# TPS6273x.net
KiCad netlist of a schematic drawn in EAGLE
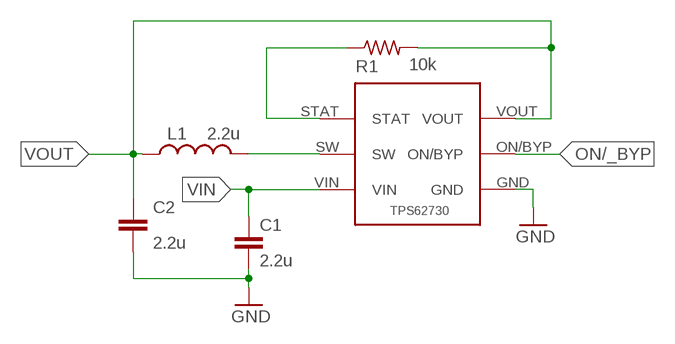
[diagram p0: schematic, sheet 1]

(export (version "E")
  (design (tool "Eeschema 10.0.6"))
  (components
    (comp (ref "C1")
      (value "2.2u")
      (footprint "eagle-import:C0603")
      (libsource (lib "eagle-import") (part "C-EUC0603"))
    )
    (comp (ref "C2")
      (value "2.2u")
      (footprint "eagle-import:C0603")
      (libsource (lib "eagle-import") (part "C-EUC0603"))
    )
    (comp (ref "L1")
      (value "2.2u")
      (footprint "eagle-import:L1210")
      (libsource (lib "eagle-import") (part "L-USL1210"))
    )
    (comp (ref "R1")
      (value "10k")
      (footprint "eagle-import:R0603")
      (libsource (lib "eagle-import") (part "R-US_R0603"))
    )
    (comp (ref "U$1")
      (value "TPS62730")
      (footprint "eagle-import:TPS62730")
      (libsource (lib "eagle-import") (part "TPS62730"))
    )
  )
  (nets
    (net (code "1") (name "GND") (class "Default")
      (node (ref "C1") (pin "2") (pinfunction "2_2") (pintype "passive"))
      (node (ref "C2") (pin "2") (pinfunction "2_2") (pintype "passive"))
      (node (ref "U$1") (pin "GND") (pinfunction "GND_GND") (pintype "bidirectional"))
    )
    (net (code "2") (name "Net-(L1-Pad2)") (class "Default")
      (node (ref "L1") (pin "2") (pinfunction "2_2") (pintype "passive"))
      (node (ref "U$1") (pin "SW") (pinfunction "SW_SW") (pintype "bidirectional"))
    )
    (net (code "3") (name "Net-(R1-Pad1)") (class "Default")
      (node (ref "R1") (pin "1") (pinfunction "1_1") (pintype "passive"))
      (node (ref "U$1") (pin "STAT") (pinfunction "STAT_STAT") (pintype "bidirectional"))
    )
    (net (code "4") (name "ON{slash}_BYP") (class "Default")
      (node (ref "U$1") (pin "ON/BYP") (pinfunction "ON/BYP_ON/BYP") (pintype "bidirectional"))
    )
    (net (code "5") (name "VIN") (class "Default")
      (node (ref "C1") (pin "1") (pinfunction "1_1") (pintype "passive"))
      (node (ref "U$1") (pin "VIN") (pinfunction "VIN_VIN") (pintype "bidirectional"))
    )
    (net (code "6") (name "VOUT") (class "Default")
      (node (ref "C2") (pin "1") (pinfunction "1_1") (pintype "passive"))
      (node (ref "L1") (pin "1") (pinfunction "1_1") (pintype "passive"))
      (node (ref "R1") (pin "2") (pinfunction "2_2") (pintype "passive"))
      (node (ref "U$1") (pin "VOUT") (pinfunction "VOUT_VOUT") (pintype "bidirectional"))
    )
  )
)
